# PMIC.net
KiCad netlist of a schematic drawn in Altium Designer
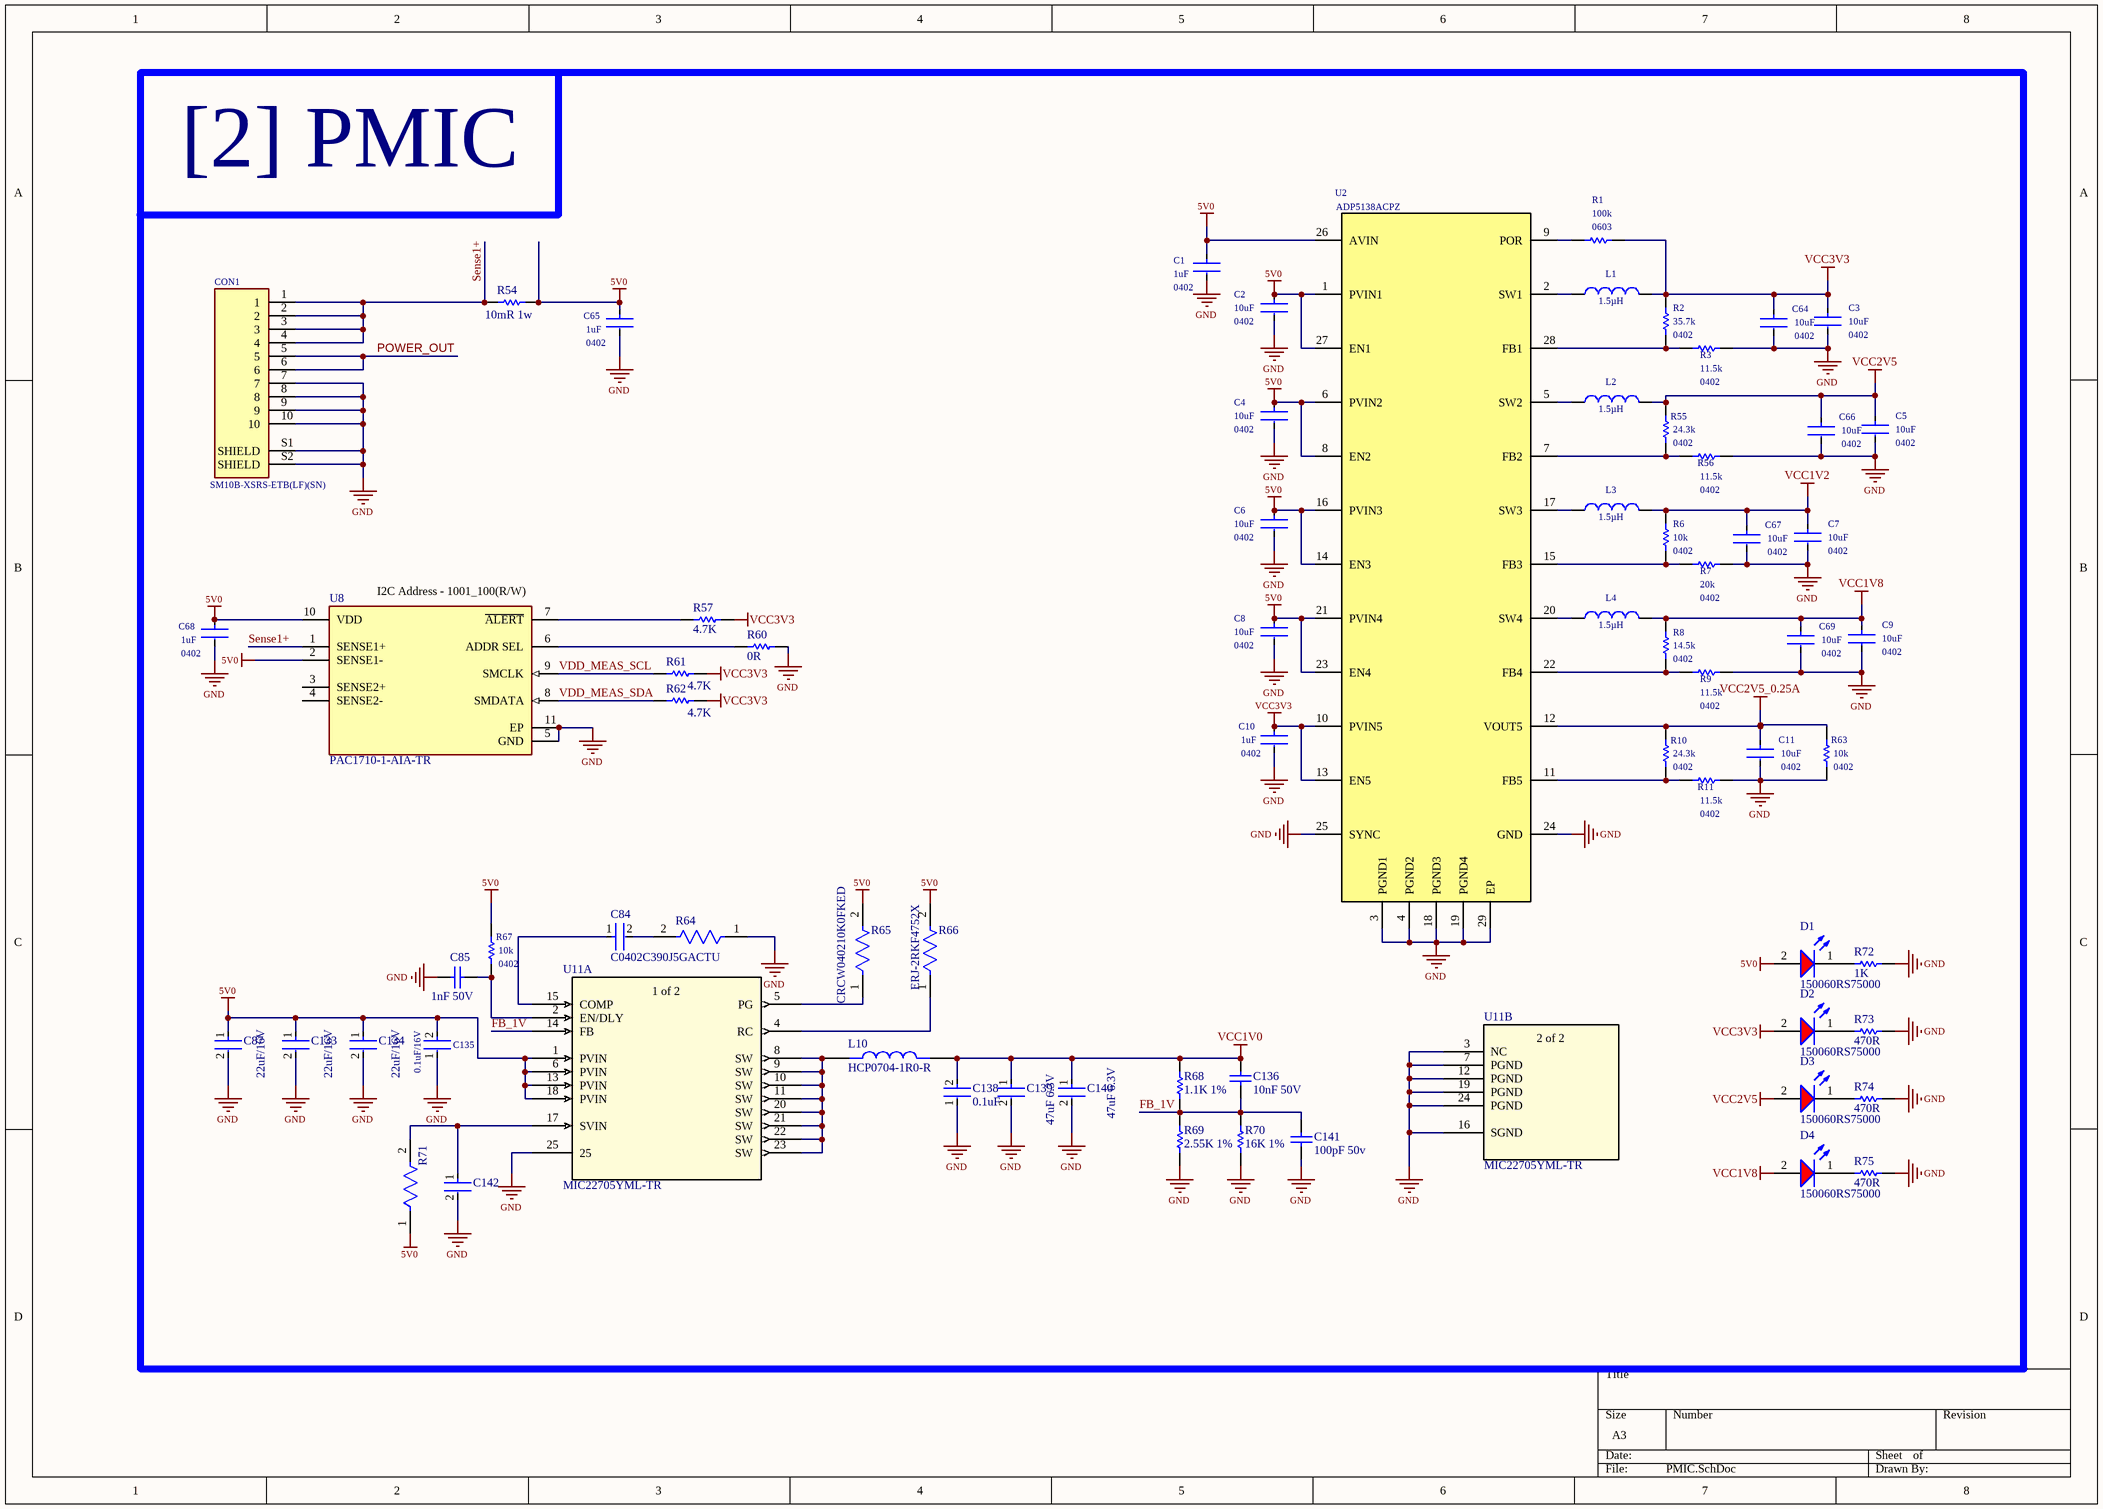
[diagram p0: PMIC.SchDoc]

(export (version "E")
  (design (tool "Eeschema 10.0.6"))
  (components
    (comp (ref "C1")
      (value "EMK105BJ105KV-F")
      (footprint "PCB_Display_Doru:FP-0402-L_1_0_0_05-W_0_5-IPC_A")
      (description "None")
      (fields
        (field (name "TOLERANCE") "10%")
        (field (name "CASE/PACKAGE") "0402")
        (field (name "CAPACITANCE") "1uF")
      )
      (libsource (lib "Camera_PCB_proj") (part "b4654b650e69147ec39a6b967a45e02"))
    )
    (comp (ref "C2")
      (value "GRM155R60J106ME44D")
      (footprint "FP-GRM155-0_2-IPC_B")
      (description "CAP CER 10UF 6.3V X5R 0402")
      (fields
        (field (name "VOLTAGE") "6.3V")
        (field (name "TOLERANCE") "20%")
        (field (name "CASE/PACKAGE") "0402")
        (field (name "CAPACITANCE") "10uF")
      )
      (libsource (lib "Camera_PCB_proj") (part "b4654b650e69147ec39a6b967a45e02"))
    )
    (comp (ref "C3")
      (value "GRM155R60J106ME44D")
      (footprint "PCB_Display_Doru:FP-GRM155-0_2-IPC_B")
      (description "CAP CER 10UF 6.3V X5R 0402")
      (fields
        (field (name "VOLTAGE") "6.3V")
        (field (name "TOLERANCE") "20%")
        (field (name "CASE/PACKAGE") "0402")
        (field (name "CAPACITANCE") "10uF")
      )
      (libsource (lib "Camera_PCB_proj") (part "b4654b650e69147ec39a6b967a45e02"))
    )
    (comp (ref "C4")
      (value "GRM155R60J106ME44D")
      (footprint "FP-GRM155-0_2-IPC_B")
      (description "CAP CER 10UF 6.3V X5R 0402")
      (fields
        (field (name "VOLTAGE") "6.3V")
        (field (name "TOLERANCE") "20%")
        (field (name "CASE/PACKAGE") "0402")
        (field (name "CAPACITANCE") "10uF")
      )
      (libsource (lib "Camera_PCB_proj") (part "b4654b650e69147ec39a6b967a45e02"))
    )
    (comp (ref "C5")
      (value "GRM155R60J106ME44D")
      (footprint "FP-GRM155-0_2-IPC_B")
      (description "CAP CER 10UF 6.3V X5R 0402")
      (fields
        (field (name "VOLTAGE") "6.3V")
        (field (name "TOLERANCE") "20%")
        (field (name "CASE/PACKAGE") "0402")
        (field (name "CAPACITANCE") "10uF")
      )
      (libsource (lib "Camera_PCB_proj") (part "b4654b650e69147ec39a6b967a45e02"))
    )
    (comp (ref "C6")
      (value "GRM155R60J106ME44D")
      (footprint "FP-GRM155-0_2-IPC_B")
      (description "CAP CER 10UF 6.3V X5R 0402")
      (fields
        (field (name "VOLTAGE") "6.3V")
        (field (name "TOLERANCE") "20%")
        (field (name "CASE/PACKAGE") "0402")
        (field (name "CAPACITANCE") "10uF")
      )
      (libsource (lib "Camera_PCB_proj") (part "b4654b650e69147ec39a6b967a45e02"))
    )
    (comp (ref "C7")
      (value "GRM155R60J106ME44D")
      (footprint "PCB_Display_Doru:FP-GRM155-0_2-IPC_B")
      (description "CAP CER 10UF 6.3V X5R 0402")
      (fields
        (field (name "VOLTAGE") "6.3V")
        (field (name "TOLERANCE") "20%")
        (field (name "CASE/PACKAGE") "0402")
        (field (name "CAPACITANCE") "10uF")
      )
      (libsource (lib "Camera_PCB_proj") (part "b4654b650e69147ec39a6b967a45e02"))
    )
    (comp (ref "C8")
      (value "GRM155R60J106ME44D")
      (footprint "FP-GRM155-0_2-IPC_B")
      (description "CAP CER 10UF 6.3V X5R 0402")
      (fields
        (field (name "VOLTAGE") "6.3V")
        (field (name "TOLERANCE") "20%")
        (field (name "CASE/PACKAGE") "0402")
        (field (name "CAPACITANCE") "10uF")
      )
      (libsource (lib "Camera_PCB_proj") (part "b4654b650e69147ec39a6b967a45e02"))
    )
    (comp (ref "C9")
      (value "GRM155R60J106ME44D")
      (footprint "PCB_Display_Doru:FP-GRM155-0_2-IPC_B")
      (description "CAP CER 10UF 6.3V X5R 0402")
      (fields
        (field (name "VOLTAGE") "6.3V")
        (field (name "TOLERANCE") "20%")
        (field (name "CASE/PACKAGE") "0402")
        (field (name "CAPACITANCE") "10uF")
      )
      (libsource (lib "Camera_PCB_proj") (part "b4654b650e69147ec39a6b967a45e02"))
    )
    (comp (ref "C10")
      (value "EMK105BJ105KV-F")
      (footprint "PCB_Display_Doru:FP-0402-L_1_0_0_05-W_0_5-IPC_A")
      (description "None")
      (fields
        (field (name "TOLERANCE") "10%")
        (field (name "CASE/PACKAGE") "0402")
        (field (name "CAPACITANCE") "1uF")
      )
      (libsource (lib "Camera_PCB_proj") (part "b4654b650e69147ec39a6b967a45e02"))
    )
    (comp (ref "C11")
      (value "GRM155R60J106ME44D")
      (footprint "PCB_Display_Doru:FP-GRM155-0_2-IPC_B")
      (description "CAP CER 10UF 6.3V X5R 0402")
      (fields
        (field (name "VOLTAGE") "6.3V")
        (field (name "TOLERANCE") "20%")
        (field (name "CASE/PACKAGE") "0402")
        (field (name "CAPACITANCE") "10uF")
      )
      (libsource (lib "Camera_PCB_proj") (part "b4654b650e69147ec39a6b967a45e02"))
    )
    (comp (ref "C64")
      (value "GRM155R60J106ME44D")
      (footprint "FP-GRM155-0_2-IPC_B")
      (description "CAP CER 10UF 6.3V X5R 0402")
      (fields
        (field (name "VOLTAGE") "6.3V")
        (field (name "TOLERANCE") "20%")
        (field (name "CASE/PACKAGE") "0402")
        (field (name "CAPACITANCE") "10uF")
      )
      (libsource (lib "Camera_PCB_proj") (part "b4654b650e69147ec39a6b967a45e02"))
    )
    (comp (ref "C65")
      (value "EMK105BJ105KV-F")
      (footprint "FP-0402-L_1_0_0_05-W_0_5-IPC_A")
      (description "None")
      (fields
        (field (name "TOLERANCE") "10%")
        (field (name "CASE/PACKAGE") "0402")
        (field (name "CAPACITANCE") "1uF")
      )
      (libsource (lib "Camera_PCB_proj") (part "b4654b650e69147ec39a6b967a45e02"))
    )
    (comp (ref "C66")
      (value "GRM155R60J106ME44D")
      (footprint "FP-GRM155-0_2-IPC_B")
      (description "CAP CER 10UF 6.3V X5R 0402")
      (fields
        (field (name "VOLTAGE") "6.3V")
        (field (name "TOLERANCE") "20%")
        (field (name "CASE/PACKAGE") "0402")
        (field (name "CAPACITANCE") "10uF")
      )
      (libsource (lib "Camera_PCB_proj") (part "b4654b650e69147ec39a6b967a45e02"))
    )
    (comp (ref "C67")
      (value "GRM155R60J106ME44D")
      (footprint "FP-GRM155-0_2-IPC_B")
      (description "CAP CER 10UF 6.3V X5R 0402")
      (fields
        (field (name "VOLTAGE") "6.3V")
        (field (name "TOLERANCE") "20%")
        (field (name "CASE/PACKAGE") "0402")
        (field (name "CAPACITANCE") "10uF")
      )
      (libsource (lib "Camera_PCB_proj") (part "b4654b650e69147ec39a6b967a45e02"))
    )
    (comp (ref "C68")
      (value "EMK105BJ105KV-F")
      (footprint "FP-0402-L_1_0_0_05-W_0_5-IPC_A")
      (description "None")
      (fields
        (field (name "TOLERANCE") "10%")
        (field (name "CASE/PACKAGE") "0402")
        (field (name "CAPACITANCE") "1uF")
      )
      (libsource (lib "Camera_PCB_proj") (part "b4654b650e69147ec39a6b967a45e02"))
    )
    (comp (ref "C69")
      (value "GRM155R60J106ME44D")
      (footprint "FP-GRM155-0_2-IPC_B")
      (description "CAP CER 10UF 6.3V X5R 0402")
      (fields
        (field (name "VOLTAGE") "6.3V")
        (field (name "TOLERANCE") "20%")
        (field (name "CASE/PACKAGE") "0402")
        (field (name "CAPACITANCE") "10uF")
      )
      (libsource (lib "Camera_PCB_proj") (part "b4654b650e69147ec39a6b967a45e02"))
    )
    (comp (ref "C84")
      (value "C0402C390J5GACTU")
      (footprint "FP-C0402-BB-MFG")
      (description "CAP CER 39PF 50V C0G/NP0 0402")
      (fields
        (field (name "MANUFACTURER") "Kemet")
        (field (name "OCTOPART") "https://octopart.com/c0402c390j5gactu-kemet-121734")
      )
      (libsource (lib "Altium Content Vault") (part "b4654b650e69147ec39a6b967a45e02"))
    )
    (comp (ref "C85")
      (value "1nF 50V")
      (footprint "CAPC1005X55X25ML5T10")
      (description "Chip Capacitor, 1 nF, +/- 10%, 50 V, -55 to 125 degC, 0402 (1005 Metric), RoHS, Tape and Reel")
      (fields (field (name "TOLERANCE") "10%"))
      (libsource (lib "Altium Content Vault") (part "CAP-NP-2"))
    )
    (comp (ref "C87")
      (value "22uF/16V")
      (footprint "FP-0805-L_2_0_0_2-W_1_25-IPC_A")
      (description "Multilayer Ceramic Capacitor 22uF 16V X5R 20% SMD 0805 T/R")
      (fields (field (name "TOLERANCE") "20%"))
      (libsource (lib "Altium Content Vault") (part "02cd4be3c70576c341d710602a673aa"))
    )
    (comp (ref "C133")
      (value "22uF/16V")
      (footprint "FP-0805-L_2_0_0_2-W_1_25-IPC_A")
      (description "Multilayer Ceramic Capacitor 22uF 16V X5R 20% SMD 0805 T/R")
      (fields (field (name "TOLERANCE") "20%"))
      (libsource (lib "Altium Content Vault") (part "02cd4be3c70576c341d710602a673aa"))
    )
    (comp (ref "C134")
      (value "22uF/16V")
      (footprint "FP-0805-L_2_0_0_2-W_1_25-IPC_A")
      (description "Multilayer Ceramic Capacitor 22uF 16V X5R 20% SMD 0805 T/R")
      (fields (field (name "TOLERANCE") "20%"))
      (libsource (lib "Altium Content Vault") (part "02cd4be3c70576c341d710602a673aa"))
    )
    (comp (ref "C135")
      (value "0.1uF/16V")
      (footprint "FP-GRM15-MFG")
      (description "CAP CER 0.1UF 16V X7R 0402")
      (fields (field (name "MANUFACTURER PART NUMBER") "GRM155R71C104KA88D") (field (name "TOLERANCE") "10%"))
      (libsource (lib "Altium Content Vault") (part "236180d848d6139a670b325ea6854c9"))
    )
    (comp (ref "C136")
      (value "10nF 50V")
      (footprint "CAPC1005X55X30LL05T10")
      (fields (field (name "PART NUMBER") "C0402C103K5RACTU") (field (name "MANUFACTURER") "Kemet"))
      (libsource (lib "Altium Content Vault") (part "CAP"))
    )
    (comp (ref "C138")
      (value "0.1uF")
      (footprint "FP-GRM15-MFG")
      (description "CAP CER 0.1UF 16V X7R 0402")
      (fields (field (name "MANUFACTURER PART NUMBER") "GRM155R71C104KA88D") (field (name "TOLERANCE") "10%"))
      (libsource (lib "Altium Content Vault") (part "236180d848d6139a670b325ea6854c9"))
    )
    (comp (ref "C139")
      (value "47uF 6.3V")
      (footprint "FP-C0805C476M9PACTU-MFG")
      (description "CAP CER 47UF 6.3V X5R 0805")
      (fields (field (name "VOLTAGE") "6.3V") (field (name "TOLERANCE") "20%"))
      (libsource (lib "Altium Content Vault") (part "11868f565c42a9108669ba33697ecf6"))
    )
    (comp (ref "C140")
      (value "47uF 6.3V")
      (footprint "FP-C0805C476M9PACTU-MFG")
      (description "CAP CER 47UF 6.3V X5R 0805")
      (fields (field (name "VOLTAGE") "6.3V") (field (name "TOLERANCE") "20%"))
      (libsource (lib "Altium Content Vault") (part "11868f565c42a9108669ba33697ecf6"))
    )
    (comp (ref "C141")
      (value "100pF 50v")
      (footprint "CAPC1005X55X25ML05T10")
      (fields (field (name "MANUFACTURER") "Murata") (field (name "PART NUMBER") "GRM1555C1H101JA01D"))
      (libsource (lib "Altium Content Vault") (part "CAP"))
    )
    (comp (ref "C142")
      (value "C1005X5R1C225K050BC")
      (footprint "FP-C1005-050-0_05-IPC_A")
      (description "Multilayer Ceramic Capacitors 2.2μF ±10% 16V X5R SMD 0402")
      (fields (field (name "TOLERANCE") "10%"))
      (libsource (lib "Altium Content Vault") (part "b4654b650e69147ec39a6b967a45e02"))
    )
    (comp (ref "CON1")
      (value "SM10B-XSRS-ETB(LF)(SN)")
      (footprint "PCB_Display_Doru:SM10B-XSRS-ETB")
      (fields (field (name "PART_NUMBER") "J00001"))
      (libsource (lib "PCB_Display_Doru") (part "SM10B-XSRS-ETB(LF)(SN)"))
    )
    (comp (ref "D1")
      (value "150060RS75000")
      (footprint "WL-SMCW_0603_150060xx75000")
      (description "LED Low-Power Uni-Color Red 630nm 2V 2-Pin Chip 0603(1608Metric) T/R")
      (libsource (lib "Altium Content Vault") (part "LED_Red_2A-1K"))
    )
    (comp (ref "D2")
      (value "150060RS75000")
      (footprint "WL-SMCW_0603_150060xx75000")
      (description "LED Low-Power Uni-Color Red 630nm 2V 2-Pin Chip 0603(1608Metric) T/R")
      (libsource (lib "Altium Content Vault") (part "LED_Red_2A-1K"))
    )
    (comp (ref "D3")
      (value "150060RS75000")
      (footprint "WL-SMCW_0603_150060xx75000")
      (description "LED Low-Power Uni-Color Red 630nm 2V 2-Pin Chip 0603(1608Metric) T/R")
      (libsource (lib "Altium Content Vault") (part "LED_Red_2A-1K"))
    )
    (comp (ref "D4")
      (value "150060RS75000")
      (footprint "WL-SMCW_0603_150060xx75000")
      (description "LED Low-Power Uni-Color Red 630nm 2V 2-Pin Chip 0603(1608Metric) T/R")
      (libsource (lib "Altium Content Vault") (part "LED_Red_2A-1K"))
    )
    (comp (ref "L1")
      (value "744031001")
      (footprint "PCB_Display_Doru:WE-TPC-3816-S")
      (description "SMD Shielded Tiny Power Inductor WE-TPC, L = 1.50 µH")
      (fields (field (name "INDUCTANCE") "1.5µH"))
      (libsource (lib "Camera_PCB_proj") (part "PAS-IND-INDUCTOR-2"))
    )
    (comp (ref "L2")
      (value "744031001")
      (footprint "PCB_Display_Doru:WE-TPC-3816-S")
      (description "SMD Shielded Tiny Power Inductor WE-TPC, L = 1.50 µH")
      (fields (field (name "INDUCTANCE") "1.5µH"))
      (libsource (lib "Camera_PCB_proj") (part "PAS-IND-INDUCTOR-2"))
    )
    (comp (ref "L3")
      (value "744031001")
      (footprint "PCB_Display_Doru:WE-TPC-3816-S")
      (description "SMD Shielded Tiny Power Inductor WE-TPC, L = 1.50 µH")
      (fields (field (name "INDUCTANCE") "1.5µH"))
      (libsource (lib "Camera_PCB_proj") (part "PAS-IND-INDUCTOR-2"))
    )
    (comp (ref "L4")
      (value "744031001")
      (footprint "PCB_Display_Doru:WE-TPC-3816-S")
      (description "SMD Shielded Tiny Power Inductor WE-TPC, L = 1.50 µH")
      (fields (field (name "INDUCTANCE") "1.5µH"))
      (libsource (lib "Camera_PCB_proj") (part "PAS-IND-INDUCTOR-2"))
    )
    (comp (ref "L10")
      (value "HCP0704-1R0-R")
      (footprint "PCB_Display_Doru:IND_SCIHP1367-100M")
      (fields (field (name "MP") "SCIHP1367-3R3M") (field (name "MF") "Signal Transformer"))
      (libsource (lib "PCB_Display_Doru") (part "SCIHP1367-3R3M"))
    )
    (comp (ref "R1")
      (value "100k")
      (footprint "PCB_Display_Doru:RESC1608X55X30ML20T20")
      (fields
        (field (name "PART NUMBER") "ERA3AEB104V")
        (field (name "MANUFACTURER") "Panasonic")
        (field (name "PACKAGE") "0603")
      )
      (libsource (lib "Camera_PCB_proj") (part "RES"))
    )
    (comp (ref "R2")
      (value "RC0402FR-0735K7L")
      (footprint "RESC1005X40X25NL05T10")
      (fields
        (field (name "MANUFACTURER") "Yageo / Phycomp")
        (field (name "PARAMETER 1") "35.7k")
        (field (name "PARAMETER 2") "0402")
      )
      (libsource (lib "Camera_PCB_proj") (part "RES"))
    )
    (comp (ref "R3")
      (value "RC0402FR-0711K5L")
      (footprint "PCB_Display_Doru:RESC1005X40X25NL05T10")
      (fields
        (field (name "MANUFACTURER") "Yageo / Phycomp")
        (field (name "PARAMETER 3") "11.5k")
        (field (name "PARAMETER 4") "0402")
      )
      (libsource (lib "Camera_PCB_proj") (part "RES"))
    )
    (comp (ref "R6")
      (value "RC0402FR-0710KL")
      (footprint "PCB_Display_Doru:RESC1005X40X25NL05T10")
      (fields
        (field (name "MANUFACTURER") "Yageo / Phycomp")
        (field (name "PARAMETER 3") "10k")
        (field (name "PARAMETER 4") "0402")
      )
      (libsource (lib "Camera_PCB_proj") (part "RES"))
    )
    (comp (ref "R7")
      (value "RC0402FR-0720KL")
      (footprint "PCB_Display_Doru:RESC1005X40X25NL05T10")
      (fields
        (field (name "MANUFACTURER") "Yageo / Phycomp")
        (field (name "PARAMETER 3") "20k")
        (field (name "PARAMETER 4") "0402")
      )
      (libsource (lib "Camera_PCB_proj") (part "RES"))
    )
    (comp (ref "R8")
      (value "RN73H1ETTP1452F25")
      (footprint "PCB_Display_Doru:RESC1005X40N")
      (fields (field (name "PARAMETER 3") "14.5k") (field (name "PARAMETER 4") "0402"))
      (libsource (lib "Camera_PCB_proj") (part "RN73H1ETTP1452F25"))
    )
    (comp (ref "R9")
      (value "RC0402FR-0711K5L")
      (footprint "PCB_Display_Doru:RESC1005X40X25NL05T10")
      (fields
        (field (name "MANUFACTURER") "Yageo / Phycomp")
        (field (name "PARAMETER 3") "11.5k")
        (field (name "PARAMETER 4") "0402")
      )
      (libsource (lib "Camera_PCB_proj") (part "RES"))
    )
    (comp (ref "R10")
      (value "RC0402FR-0724K3L")
      (footprint "PCB_Display_Doru:RESC1005X40X25NL05T10")
      (fields
        (field (name "MANUFACTURER") "Yageo")
        (field (name "PARAMETER 3") "24.3k")
        (field (name "PARAMETER 4") "0402")
      )
      (libsource (lib "Camera_PCB_proj") (part "RES"))
    )
    (comp (ref "R11")
      (value "RC0402FR-0711K5L")
      (footprint "PCB_Display_Doru:RESC1005X40X25NL05T10")
      (fields
        (field (name "MANUFACTURER") "Yageo / Phycomp")
        (field (name "PARAMETER 3") "11.5k")
        (field (name "PARAMETER 4") "0402")
      )
      (libsource (lib "Camera_PCB_proj") (part "RES"))
    )
    (comp (ref "R54")
      (value "10mR 1w")
      (footprint "RESC2013X50X30LL20T20")
      (fields (field (name "MANUFACTURER") "Vishay Dale") (field (name "PART NUMBER") "CRCW08050000Z0EA"))
      (libsource (lib "Altium Content Vault") (part "RES"))
    )
    (comp (ref "R55")
      (value "RC0402FR-0724K3L")
      (footprint "RESC1005X40X25NL05T10")
      (fields
        (field (name "MANUFACTURER") "Yageo")
        (field (name "PARAMETER 3") "24.3k")
        (field (name "PARAMETER 4") "0402")
      )
      (libsource (lib "Camera_PCB_proj") (part "RES"))
    )
    (comp (ref "R56")
      (value "RC0402FR-0711K5L")
      (footprint "RESC1005X40X25NL05T10")
      (fields
        (field (name "MANUFACTURER") "Yageo / Phycomp")
        (field (name "PARAMETER 3") "11.5k")
        (field (name "PARAMETER 4") "0402")
      )
      (libsource (lib "Camera_PCB_proj") (part "RES"))
    )
    (comp (ref "R57")
      (value "4.7K")
      (footprint "RESC1005X40X25LL05T05")
      (description "Chip Resistor, 4.7 KOhm, +/- 1%, 0.1 W, -55 to 155 degC, 0402 (1005 Metric), RoHS, Tape and Reel")
      (fields (field (name "TOLERANCE") "1%") (field (name "PARTNUMBER") "ERJ-2RKF4701X"))
      (libsource (lib "Altium Content Vault") (part "RES-2"))
    )
    (comp (ref "R60")
      (value "0R")
      (footprint "RESC1608X55X25ML10T15")
      (description "Chip Resistor, 0 Ohm, +/- 5%, 0.1 W, -55 to 155 degC, 0603 (1608 Metric), RoHS, Tape and Reel")
      (fields (field (name "TOLERANCE") "5%") (field (name "MANUFACTURER") "Yageo"))
      (libsource (lib "Altium Content Vault") (part "RES-2"))
    )
    (comp (ref "R61")
      (value "4.7K")
      (footprint "RESC1005X40X25LL05T05")
      (description "Chip Resistor, 4.7 KOhm, +/- 1%, 0.1 W, -55 to 155 degC, 0402 (1005 Metric), RoHS, Tape and Reel")
      (fields (field (name "TOLERANCE") "1%") (field (name "PARTNUMBER") "ERJ-2RKF4701X"))
      (libsource (lib "Altium Content Vault") (part "RES-2"))
    )
    (comp (ref "R62")
      (value "4.7K")
      (footprint "RESC1005X40X25LL05T05")
      (description "Chip Resistor, 4.7 KOhm, +/- 1%, 0.1 W, -55 to 155 degC, 0402 (1005 Metric), RoHS, Tape and Reel")
      (fields (field (name "TOLERANCE") "1%") (field (name "PARTNUMBER") "ERJ-2RKF4701X"))
      (libsource (lib "Altium Content Vault") (part "RES-2"))
    )
    (comp (ref "R63")
      (value "RC0402FR-0710KL")
      (footprint "RESC1005X40X25NL05T10")
      (fields
        (field (name "MANUFACTURER") "Yageo / Phycomp")
        (field (name "PARAMETER 3") "10k")
        (field (name "PARAMETER 4") "0402")
      )
      (libsource (lib "Camera_PCB_proj") (part "RES"))
    )
    (comp (ref "R64")
      (value "CRCW040220K0FKED")
      (footprint "FP-CRCW0402-e3-IPC_B")
      (description "RES Thick Film, 20kΩ, 1%, 0.063W, 100ppm/°C, 0402")
      (fields (field (name "TOLERANCE") "1%"))
      (libsource (lib "Altium Content Vault") (part "1029c3af85768c4190bb7ad29bc67b5"))
    )
    (comp (ref "R65")
      (value "CRCW040210K0FKED")
      (footprint "FP-CRCW0402-e3-IPC_B")
      (description "RES SMD 10K OHM 1% 1/16W 0402")
      (fields (field (name "TOLERANCE") "1%"))
      (libsource (lib "Altium Content Vault") (part "1029c3af85768c4190bb7ad29bc67b5"))
    )
    (comp (ref "R66")
      (value "ERJ-2RKF4752X")
      (footprint "FP-ERJ2RK-IPC_A")
      (description "RES SMD 47.5K OHM 1% 1/10W 0402")
      (fields (field (name "TOLERANCE") "1%"))
      (libsource (lib "Altium Content Vault") (part "1029c3af85768c4190bb7ad29bc67b5"))
    )
    (comp (ref "R67")
      (value "RC0402FR-0710KL")
      (footprint "RESC1005X40X25NL05T10")
      (fields
        (field (name "MANUFACTURER") "Yageo / Phycomp")
        (field (name "PARAMETER 3") "10k")
        (field (name "PARAMETER 4") "0402")
      )
      (libsource (lib "Camera_PCB_proj") (part "RES"))
    )
    (comp (ref "R68")
      (value "1.1K 1%")
      (footprint "RESC0603X26X15ML03T05")
      (fields (field (name "MANUFACTURER") "Multicomp") (field (name "PART NUMBER") "MCRE000141"))
      (libsource (lib "Altium Content Vault") (part "RES"))
    )
    (comp (ref "R69")
      (value "2.55K 1%")
      (footprint "RESC2013X60X40NL20T25")
      (fields (field (name "MANUFACTURER") "Panasonic") (field (name "PART NUMBER") "ERA6AEB2551V"))
      (libsource (lib "Altium Content Vault") (part "RES"))
    )
    (comp (ref "R70")
      (value "16K 1%")
      (footprint "RESC1005X40X25ML05T10")
      (fields (field (name "MANUFACTURER") "Yageo / Phycomp") (field (name "PART NUMBER") "RC0402FR-0716KL"))
      (libsource (lib "Altium Content Vault") (part "RES"))
    )
    (comp (ref "R71")
      (value "CRCW04022R20FKED")
      (footprint "FP-CRCW0402-e3-IPC_C")
      (description "RES Thick Film, 2.2Ω, 1%, 0.063W, 100ppm/°C, 0402")
      (fields (field (name "TOLERANCE") "1%"))
      (libsource (lib "Altium Content Vault") (part "1029c3af85768c4190bb7ad29bc67b5"))
    )
    (comp (ref "R72")
      (value "1K")
      (footprint "RESC1005X40X25ML05T10")
      (fields (field (name "PART NUMBER") "RC0402FR-07470RL") (field (name "MANUFACTURER") "Yageo / Phycomp"))
      (libsource (lib "Altium Content Vault") (part "RES"))
    )
    (comp (ref "R73")
      (value "470R")
      (footprint "RESC1005X40X25ML05T10")
      (fields (field (name "PART NUMBER") "RC0402FR-07470RL") (field (name "MANUFACTURER") "Yageo / Phycomp"))
      (libsource (lib "Altium Content Vault") (part "RES"))
    )
    (comp (ref "R74")
      (value "470R")
      (footprint "RESC1005X40X25ML05T10")
      (fields (field (name "PART NUMBER") "RC0402FR-07470RL") (field (name "MANUFACTURER") "Yageo / Phycomp"))
      (libsource (lib "Altium Content Vault") (part "RES"))
    )
    (comp (ref "R75")
      (value "470R")
      (footprint "RESC1005X40X25ML05T10")
      (fields (field (name "PART NUMBER") "RC0402FR-07470RL") (field (name "MANUFACTURER") "Yageo / Phycomp"))
      (libsource (lib "Altium Content Vault") (part "RES"))
    )
    (comp (ref "U2")
      (value "ADP5138ACPZ")
      (footprint "PCB_Display_Doru:CP_28_5")
      (description "No Description Available")
      (fields (field (name "COPYRIGHT") "Copyright (C) 2021 Accelerated Designs. All rights reserved"))
      (libsource (lib "Camera_PCB_proj") (part "ADP5138ACPZ"))
    )
    (comp (ref "U8")
      (value "PAC1710-1-AIA-TR")
      (footprint "FP-C04-206-MFG")
      (description "IC CURRENT SENSE MON SGL 10VDFN")
      (libsource (lib "Altium Content Vault") (part "b864e3dd72ada8881c061bb5f7a5dca"))
    )
    (comp (ref "U11")
      (value "MIC22705YML-TR")
      (footprint "MLF-24_ML_MCH")
      (description "No Description Available")
      (libsource (lib "PCB_Display_Doru") (part "MIC22705YML-TR"))
    )
  )
  (nets
    (net (code "1") (name "/FB_1V") (class "Default")
      (node (ref "C136") (pin "1") (pinfunction "1_1") (pintype "passive"))
      (node (ref "C141") (pin "2") (pinfunction "2_2") (pintype "passive"))
      (node (ref "R68") (pin "1") (pinfunction "1_1") (pintype "passive"))
      (node (ref "R69") (pin "2") (pinfunction "2_2") (pintype "passive"))
      (node (ref "R70") (pin "2") (pinfunction "2_2") (pintype "passive"))
      (node (ref "U11") (pin "14") (pinfunction "FB_14") (pintype "input"))
    )
    (net (code "2") (name "/POWER_OUT") (class "Default")
      (node (ref "CON1") (pin "5") (pinfunction "5_5") (pintype "passive"))
      (node (ref "CON1") (pin "6") (pinfunction "6_6") (pintype "passive"))
    )
    (net (code "3") (name "/Sense1+") (class "Default")
      (node (ref "CON1") (pin "1") (pinfunction "1_1") (pintype "passive"))
      (node (ref "CON1") (pin "2") (pinfunction "2_2") (pintype "passive"))
      (node (ref "CON1") (pin "3") (pinfunction "3_3") (pintype "passive"))
      (node (ref "CON1") (pin "4") (pinfunction "4_4") (pintype "passive"))
      (node (ref "R54") (pin "1") (pinfunction "1_1") (pintype "passive"))
      (node (ref "U8") (pin "1") (pinfunction "SENSE1+_1") (pintype "passive"))
    )
    (net (code "4") (name "/VDD_MEAS_SCL") (class "Default")
      (node (ref "R61") (pin "1") (pinfunction "1_1") (pintype "passive"))
      (node (ref "U8") (pin "9") (pinfunction "SMCLK_9") (pintype "input"))
    )
    (net (code "5") (name "/VDD_MEAS_SDA") (class "Default")
      (node (ref "R62") (pin "1") (pinfunction "1_1") (pintype "passive"))
      (node (ref "U8") (pin "8") (pinfunction "SMDATA_8") (pintype "input"))
    )
    (net (code "6") (name "5V0") (class "Default")
      (node (ref "C1") (pin "1") (pinfunction "1_1") (pintype "passive"))
      (node (ref "C133") (pin "1") (pinfunction "1_1") (pintype "passive"))
      (node (ref "C134") (pin "1") (pinfunction "1_1") (pintype "passive"))
      (node (ref "C135") (pin "2") (pinfunction "2_2") (pintype "passive"))
      (node (ref "C2") (pin "1") (pinfunction "1_1") (pintype "passive"))
      (node (ref "C4") (pin "1") (pinfunction "1_1") (pintype "passive"))
      (node (ref "C6") (pin "1") (pinfunction "1_1") (pintype "passive"))
      (node (ref "C65") (pin "1") (pinfunction "1_1") (pintype "passive"))
      (node (ref "C68") (pin "1") (pinfunction "1_1") (pintype "passive"))
      (node (ref "C8") (pin "1") (pinfunction "1_1") (pintype "passive"))
      (node (ref "C87") (pin "1") (pinfunction "1_1") (pintype "passive"))
      (node (ref "D1") (pin "2") (pinfunction "A_2") (pintype "passive"))
      (node (ref "R54") (pin "2") (pinfunction "2_2") (pintype "passive"))
      (node (ref "R65") (pin "2") (pinfunction "2_2") (pintype "passive"))
      (node (ref "R66") (pin "2") (pinfunction "2_2") (pintype "passive"))
      (node (ref "R67") (pin "2") (pinfunction "2_2") (pintype "passive"))
      (node (ref "R71") (pin "1") (pinfunction "1_1") (pintype "passive"))
      (node (ref "U11") (pin "1") (pinfunction "PVIN_1") (pintype "input"))
      (node (ref "U11") (pin "13") (pinfunction "PVIN_13") (pintype "input"))
      (node (ref "U11") (pin "18") (pinfunction "PVIN_18") (pintype "input"))
      (node (ref "U11") (pin "6") (pinfunction "PVIN_6") (pintype "input"))
      (node (ref "U2") (pin "1") (pinfunction "PVIN1_1") (pintype "passive"))
      (node (ref "U2") (pin "14") (pinfunction "EN3_14") (pintype "passive"))
      (node (ref "U2") (pin "16") (pinfunction "PVIN3_16") (pintype "passive"))
      (node (ref "U2") (pin "21") (pinfunction "PVIN4_21") (pintype "passive"))
      (node (ref "U2") (pin "23") (pinfunction "EN4_23") (pintype "passive"))
      (node (ref "U2") (pin "26") (pinfunction "AVIN_26") (pintype "passive"))
      (node (ref "U2") (pin "27") (pinfunction "EN1_27") (pintype "passive"))
      (node (ref "U2") (pin "6") (pinfunction "PVIN2_6") (pintype "passive"))
      (node (ref "U2") (pin "8") (pinfunction "EN2_8") (pintype "passive"))
      (node (ref "U8") (pin "10") (pinfunction "VDD_10") (pintype "power_in"))
      (node (ref "U8") (pin "2") (pinfunction "SENSE1-_2") (pintype "passive"))
    )
    (net (code "7") (name "GND") (class "Default")
      (node (ref "C1") (pin "2") (pinfunction "2_2") (pintype "passive"))
      (node (ref "C10") (pin "2") (pinfunction "2_2") (pintype "passive"))
      (node (ref "C11") (pin "2") (pinfunction "2_2") (pintype "passive"))
      (node (ref "C133") (pin "2") (pinfunction "2_2") (pintype "passive"))
      (node (ref "C134") (pin "2") (pinfunction "2_2") (pintype "passive"))
      (node (ref "C135") (pin "1") (pinfunction "1_1") (pintype "passive"))
      (node (ref "C138") (pin "1") (pinfunction "1_1") (pintype "passive"))
      (node (ref "C139") (pin "2") (pinfunction "2_2") (pintype "passive"))
      (node (ref "C140") (pin "2") (pinfunction "2_2") (pintype "passive"))
      (node (ref "C141") (pin "1") (pinfunction "1_1") (pintype "passive"))
      (node (ref "C142") (pin "2") (pinfunction "2_2") (pintype "passive"))
      (node (ref "C2") (pin "2") (pinfunction "2_2") (pintype "passive"))
      (node (ref "C3") (pin "2") (pinfunction "2_2") (pintype "passive"))
      (node (ref "C4") (pin "2") (pinfunction "2_2") (pintype "passive"))
      (node (ref "C5") (pin "2") (pinfunction "2_2") (pintype "passive"))
      (node (ref "C6") (pin "2") (pinfunction "2_2") (pintype "passive"))
      (node (ref "C64") (pin "2") (pinfunction "2_2") (pintype "passive"))
      (node (ref "C65") (pin "2") (pinfunction "2_2") (pintype "passive"))
      (node (ref "C66") (pin "2") (pinfunction "2_2") (pintype "passive"))
      (node (ref "C67") (pin "2") (pinfunction "2_2") (pintype "passive"))
      (node (ref "C68") (pin "2") (pinfunction "2_2") (pintype "passive"))
      (node (ref "C69") (pin "2") (pinfunction "2_2") (pintype "passive"))
      (node (ref "C7") (pin "2") (pinfunction "2_2") (pintype "passive"))
      (node (ref "C8") (pin "2") (pinfunction "2_2") (pintype "passive"))
      (node (ref "C85") (pin "1") (pinfunction "1_1") (pintype "passive"))
      (node (ref "C87") (pin "2") (pinfunction "2_2") (pintype "passive"))
      (node (ref "C9") (pin "2") (pinfunction "2_2") (pintype "passive"))
      (node (ref "CON1") (pin "10") (pinfunction "10_10") (pintype "passive"))
      (node (ref "CON1") (pin "7") (pinfunction "7_7") (pintype "passive"))
      (node (ref "CON1") (pin "8") (pinfunction "8_8") (pintype "passive"))
      (node (ref "CON1") (pin "9") (pinfunction "9_9") (pintype "passive"))
      (node (ref "CON1") (pin "S1") (pinfunction "SHIELD_S1") (pintype "passive"))
      (node (ref "CON1") (pin "S2") (pinfunction "SHIELD_S2") (pintype "passive"))
      (node (ref "R11") (pin "2") (pinfunction "2_2") (pintype "passive"))
      (node (ref "R3") (pin "2") (pinfunction "2_2") (pintype "passive"))
      (node (ref "R56") (pin "2") (pinfunction "2_2") (pintype "passive"))
      (node (ref "R60") (pin "2") (pinfunction "2_2") (pintype "passive"))
      (node (ref "R63") (pin "1") (pinfunction "1_1") (pintype "passive"))
      (node (ref "R64") (pin "1") (pinfunction "1_1") (pintype "passive"))
      (node (ref "R69") (pin "1") (pinfunction "1_1") (pintype "passive"))
      (node (ref "R7") (pin "2") (pinfunction "2_2") (pintype "passive"))
      (node (ref "R70") (pin "1") (pinfunction "1_1") (pintype "passive"))
      (node (ref "R72") (pin "2") (pinfunction "2_2") (pintype "passive"))
      (node (ref "R73") (pin "2") (pinfunction "2_2") (pintype "passive"))
      (node (ref "R74") (pin "2") (pinfunction "2_2") (pintype "passive"))
      (node (ref "R75") (pin "2") (pinfunction "2_2") (pintype "passive"))
      (node (ref "R9") (pin "2") (pinfunction "2_2") (pintype "passive"))
      (node (ref "U11") (pin "12") (pinfunction "PGND_12") (pintype "power_in"))
      (node (ref "U11") (pin "16") (pinfunction "SGND_16") (pintype "power_in"))
      (node (ref "U11") (pin "19") (pinfunction "PGND_19") (pintype "power_in"))
      (node (ref "U11") (pin "24") (pinfunction "PGND_24") (pintype "power_in"))
      (node (ref "U11") (pin "25") (pinfunction "25_25") (pintype "passive"))
      (node (ref "U11") (pin "3") (pinfunction "NC_3") (pintype "passive"))
      (node (ref "U11") (pin "7") (pinfunction "PGND_7") (pintype "power_in"))
      (node (ref "U2") (pin "18") (pinfunction "PGND3_18") (pintype "passive"))
      (node (ref "U2") (pin "19") (pinfunction "PGND4_19") (pintype "passive"))
      (node (ref "U2") (pin "24") (pinfunction "GND_24") (pintype "passive"))
      (node (ref "U2") (pin "25") (pinfunction "SYNC_25") (pintype "passive"))
      (node (ref "U2") (pin "29") (pinfunction "EP_29") (pintype "passive"))
      (node (ref "U2") (pin "3") (pinfunction "PGND1_3") (pintype "passive"))
      (node (ref "U2") (pin "4") (pinfunction "PGND2_4") (pintype "passive"))
      (node (ref "U8") (pin "11") (pinfunction "EP_11") (pintype "power_in"))
      (node (ref "U8") (pin "5") (pinfunction "GND_5") (pintype "power_in"))
    )
    (net (code "8") (name "Net-(C84-Pad2)") (class "Default")
      (node (ref "C84") (pin "2") (pinfunction "2_2") (pintype "passive"))
      (node (ref "R64") (pin "2") (pinfunction "2_2") (pintype "passive"))
    )
    (net (code "9") (name "Net-(D1-K)") (class "Default")
      (node (ref "D1") (pin "1") (pinfunction "K_1") (pintype "passive"))
      (node (ref "R72") (pin "1") (pinfunction "1_1") (pintype "passive"))
    )
    (net (code "10") (name "Net-(D2-K)") (class "Default")
      (node (ref "D2") (pin "1") (pinfunction "K_1") (pintype "passive"))
      (node (ref "R73") (pin "1") (pinfunction "1_1") (pintype "passive"))
    )
    (net (code "11") (name "Net-(D3-K)") (class "Default")
      (node (ref "D3") (pin "1") (pinfunction "K_1") (pintype "passive"))
      (node (ref "R74") (pin "1") (pinfunction "1_1") (pintype "passive"))
    )
    (net (code "12") (name "Net-(D4-K)") (class "Default")
      (node (ref "D4") (pin "1") (pinfunction "K_1") (pintype "passive"))
      (node (ref "R75") (pin "1") (pinfunction "1_1") (pintype "passive"))
    )
    (net (code "13") (name "Net-(L10-Pad1)") (class "Default")
      (node (ref "L10") (pin "1") (pinfunction "1_1") (pintype "passive"))
      (node (ref "U11") (pin "10") (pinfunction "SW_10") (pintype "output"))
      (node (ref "U11") (pin "11") (pinfunction "SW_11") (pintype "output"))
      (node (ref "U11") (pin "20") (pinfunction "SW_20") (pintype "output"))
      (node (ref "U11") (pin "21") (pinfunction "SW_21") (pintype "output"))
      (node (ref "U11") (pin "22") (pinfunction "SW_22") (pintype "output"))
      (node (ref "U11") (pin "23") (pinfunction "SW_23") (pintype "output"))
      (node (ref "U11") (pin "8") (pinfunction "SW_8") (pintype "output"))
      (node (ref "U11") (pin "9") (pinfunction "SW_9") (pintype "output"))
    )
    (net (code "14") (name "Net-(U2-FB1)") (class "Default")
      (node (ref "R2") (pin "1") (pinfunction "1_1") (pintype "passive"))
      (node (ref "R3") (pin "1") (pinfunction "1_1") (pintype "passive"))
      (node (ref "U2") (pin "28") (pinfunction "FB1_28") (pintype "passive"))
    )
    (net (code "15") (name "Net-(U2-FB2)") (class "Default")
      (node (ref "R55") (pin "1") (pinfunction "1_1") (pintype "passive"))
      (node (ref "R56") (pin "1") (pinfunction "1_1") (pintype "passive"))
      (node (ref "U2") (pin "7") (pinfunction "FB2_7") (pintype "passive"))
    )
    (net (code "16") (name "Net-(U2-FB3)") (class "Default")
      (node (ref "R6") (pin "1") (pinfunction "1_1") (pintype "passive"))
      (node (ref "R7") (pin "1") (pinfunction "1_1") (pintype "passive"))
      (node (ref "U2") (pin "15") (pinfunction "FB3_15") (pintype "passive"))
    )
    (net (code "17") (name "Net-(U2-FB4)") (class "Default")
      (node (ref "R8") (pin "1") (pinfunction "1_1") (pintype "passive"))
      (node (ref "R9") (pin "1") (pinfunction "1_1") (pintype "passive"))
      (node (ref "U2") (pin "22") (pinfunction "FB4_22") (pintype "passive"))
    )
    (net (code "18") (name "Net-(U2-FB5)") (class "Default")
      (node (ref "R10") (pin "1") (pinfunction "1_1") (pintype "passive"))
      (node (ref "R11") (pin "1") (pinfunction "1_1") (pintype "passive"))
      (node (ref "U2") (pin "11") (pinfunction "FB5_11") (pintype "passive"))
    )
    (net (code "19") (name "Net-(U2-POR)") (class "Default")
      (node (ref "R1") (pin "1") (pinfunction "1_1") (pintype "passive"))
      (node (ref "U2") (pin "9") (pinfunction "POR_9") (pintype "passive"))
    )
    (net (code "20") (name "Net-(U2-SW1)") (class "Default")
      (node (ref "L1") (pin "1") (pinfunction "1_1") (pintype "passive"))
      (node (ref "U2") (pin "2") (pinfunction "SW1_2") (pintype "passive"))
    )
    (net (code "21") (name "Net-(U2-SW2)") (class "Default")
      (node (ref "L2") (pin "1") (pinfunction "1_1") (pintype "passive"))
      (node (ref "U2") (pin "5") (pinfunction "SW2_5") (pintype "passive"))
    )
    (net (code "22") (name "Net-(U2-SW3)") (class "Default")
      (node (ref "L3") (pin "1") (pinfunction "1_1") (pintype "passive"))
      (node (ref "U2") (pin "17") (pinfunction "SW3_17") (pintype "passive"))
    )
    (net (code "23") (name "Net-(U2-SW4)") (class "Default")
      (node (ref "L4") (pin "1") (pinfunction "1_1") (pintype "passive"))
      (node (ref "U2") (pin "20") (pinfunction "SW4_20") (pintype "passive"))
    )
    (net (code "24") (name "Net-(U8-ADDR_SEL)") (class "Default")
      (node (ref "R60") (pin "1") (pinfunction "1_1") (pintype "passive"))
      (node (ref "U8") (pin "6") (pinfunction "ADDR_SEL_6") (pintype "passive"))
    )
    (net (code "25") (name "Net-(U8-~{ALERT})") (class "Default")
      (node (ref "R57") (pin "1") (pinfunction "1_1") (pintype "passive"))
      (node (ref "U8") (pin "7") (pinfunction "~{ALERT}_7") (pintype "open_collector"))
    )
    (net (code "26") (name "Net-(U11A-COMP)") (class "Default")
      (node (ref "C84") (pin "1") (pinfunction "1_1") (pintype "passive"))
      (node (ref "U11") (pin "15") (pinfunction "COMP_15") (pintype "input"))
    )
    (net (code "27") (name "Net-(U11A-EN{slash}DLY)") (class "Default")
      (node (ref "C85") (pin "2") (pinfunction "2_2") (pintype "passive"))
      (node (ref "R67") (pin "1") (pinfunction "1_1") (pintype "passive"))
      (node (ref "U11") (pin "2") (pinfunction "EN/DLY_2") (pintype "input"))
    )
    (net (code "28") (name "Net-(U11A-PG)") (class "Default")
      (node (ref "R65") (pin "1") (pinfunction "1_1") (pintype "passive"))
      (node (ref "U11") (pin "5") (pinfunction "PG_5") (pintype "output"))
    )
    (net (code "29") (name "Net-(U11A-RC)") (class "Default")
      (node (ref "R66") (pin "1") (pinfunction "1_1") (pintype "passive"))
      (node (ref "U11") (pin "4") (pinfunction "RC_4") (pintype "output"))
    )
    (net (code "30") (name "Net-(U11A-SVIN)") (class "Default")
      (node (ref "C142") (pin "1") (pinfunction "1_1") (pintype "passive"))
      (node (ref "R71") (pin "2") (pinfunction "2_2") (pintype "passive"))
      (node (ref "U11") (pin "17") (pinfunction "SVIN_17") (pintype "input"))
    )
    (net (code "31") (name "VCC1V0") (class "Default")
      (node (ref "C136") (pin "2") (pinfunction "2_2") (pintype "passive"))
      (node (ref "C138") (pin "2") (pinfunction "2_2") (pintype "passive"))
      (node (ref "C139") (pin "1") (pinfunction "1_1") (pintype "passive"))
      (node (ref "C140") (pin "1") (pinfunction "1_1") (pintype "passive"))
      (node (ref "L10") (pin "2") (pinfunction "2_2") (pintype "passive"))
      (node (ref "R68") (pin "2") (pinfunction "2_2") (pintype "passive"))
    )
    (net (code "32") (name "VCC1V2") (class "Default")
      (node (ref "C67") (pin "1") (pinfunction "1_1") (pintype "passive"))
      (node (ref "C7") (pin "1") (pinfunction "1_1") (pintype "passive"))
      (node (ref "L3") (pin "2") (pinfunction "2_2") (pintype "passive"))
      (node (ref "R6") (pin "2") (pinfunction "2_2") (pintype "passive"))
    )
    (net (code "33") (name "VCC1V8") (class "Default")
      (node (ref "C69") (pin "1") (pinfunction "1_1") (pintype "passive"))
      (node (ref "C9") (pin "1") (pinfunction "1_1") (pintype "passive"))
      (node (ref "D4") (pin "2") (pinfunction "A_2") (pintype "passive"))
      (node (ref "L4") (pin "2") (pinfunction "2_2") (pintype "passive"))
      (node (ref "R8") (pin "2") (pinfunction "2_2") (pintype "passive"))
    )
    (net (code "34") (name "VCC2V5") (class "Default")
      (node (ref "C5") (pin "1") (pinfunction "1_1") (pintype "passive"))
      (node (ref "C66") (pin "1") (pinfunction "1_1") (pintype "passive"))
      (node (ref "D3") (pin "2") (pinfunction "A_2") (pintype "passive"))
      (node (ref "L2") (pin "2") (pinfunction "2_2") (pintype "passive"))
      (node (ref "R55") (pin "2") (pinfunction "2_2") (pintype "passive"))
    )
    (net (code "35") (name "VCC2V5_0.25A") (class "Default")
      (node (ref "C11") (pin "1") (pinfunction "1_1") (pintype "passive"))
      (node (ref "R10") (pin "2") (pinfunction "2_2") (pintype "passive"))
      (node (ref "R63") (pin "2") (pinfunction "2_2") (pintype "passive"))
      (node (ref "U2") (pin "12") (pinfunction "VOUT5_12") (pintype "passive"))
    )
    (net (code "36") (name "VCC3V3") (class "Default")
      (node (ref "C10") (pin "1") (pinfunction "1_1") (pintype "passive"))
      (node (ref "C3") (pin "1") (pinfunction "1_1") (pintype "passive"))
      (node (ref "C64") (pin "1") (pinfunction "1_1") (pintype "passive"))
      (node (ref "D2") (pin "2") (pinfunction "A_2") (pintype "passive"))
      (node (ref "L1") (pin "2") (pinfunction "2_2") (pintype "passive"))
      (node (ref "R1") (pin "2") (pinfunction "2_2") (pintype "passive"))
      (node (ref "R2") (pin "2") (pinfunction "2_2") (pintype "passive"))
      (node (ref "R57") (pin "2") (pinfunction "2_2") (pintype "passive"))
      (node (ref "R61") (pin "2") (pinfunction "2_2") (pintype "passive"))
      (node (ref "R62") (pin "2") (pinfunction "2_2") (pintype "passive"))
      (node (ref "U2") (pin "10") (pinfunction "PVIN5_10") (pintype "passive"))
      (node (ref "U2") (pin "13") (pinfunction "EN5_13") (pintype "passive"))
    )
    (net (code "37") (name "unconnected-(U8-SENSE2+-Pad3)") (class "Default")
      (node (ref "U8") (pin "3") (pinfunction "SENSE2+_3") (pintype "passive"))
    )
    (net (code "38") (name "unconnected-(U8-SENSE2--Pad4)") (class "Default")
      (node (ref "U8") (pin "4") (pinfunction "SENSE2-_4") (pintype "passive"))
    )
  )
)
